# SystemStatusBoard.net
KiCad netlist of a schematic drawn in Altium Designer
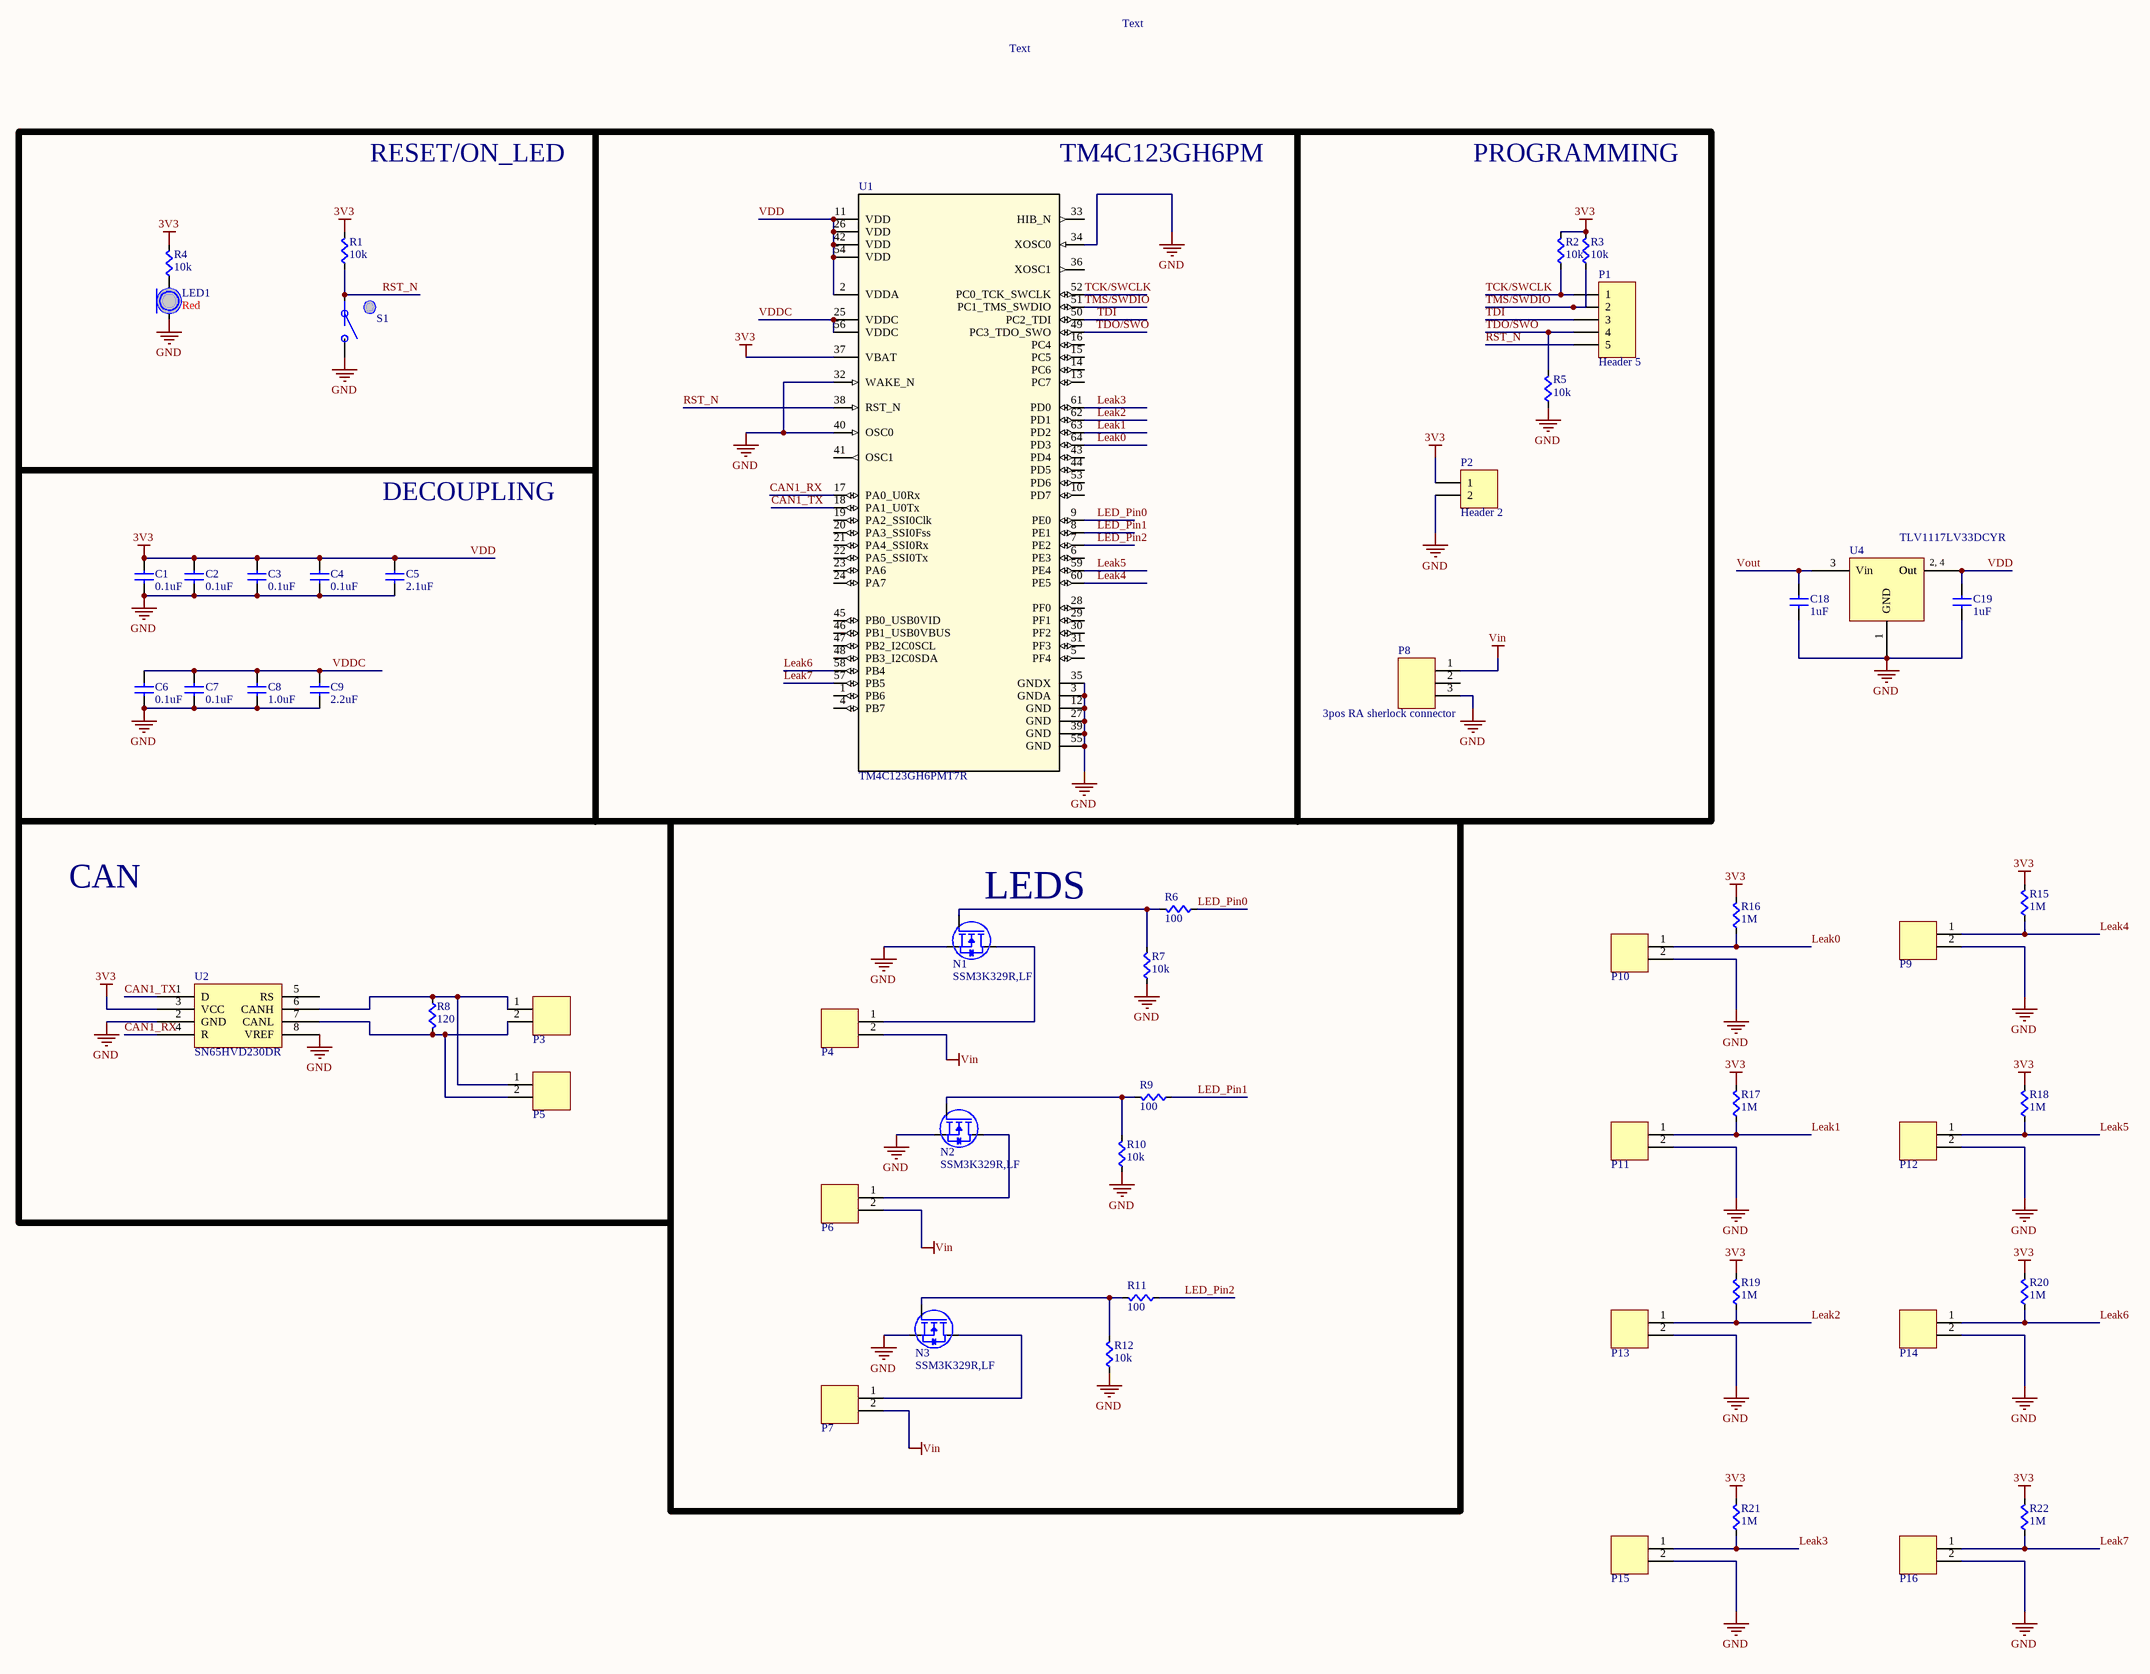
[diagram p0: SystemStatusBoard.SchDoc]

(export (version "E")
  (design (tool "Eeschema 10.0.6"))
  (components
    (comp (ref "C1")
      (value "0.1uF")
      (footprint "CAPC0603")
      (fields (field (name "Comment") "Cap"))
      (libsource (lib "SubjuGator8") (part "Cap"))
    )
    (comp (ref "C2")
      (value "0.1uF")
      (footprint "CAPC0603")
      (fields (field (name "Comment") "Cap"))
      (libsource (lib "SubjuGator8") (part "Cap"))
    )
    (comp (ref "C3")
      (value "0.1uF")
      (footprint "CAPC0603")
      (fields (field (name "Comment") "Cap"))
      (libsource (lib "SubjuGator8") (part "Cap"))
    )
    (comp (ref "C4")
      (value "0.1uF")
      (footprint "CAPC0603")
      (fields (field (name "Comment") "Cap"))
      (libsource (lib "SubjuGator8") (part "Cap"))
    )
    (comp (ref "C5")
      (value "2.1uF")
      (footprint "CAPC0603")
      (fields (field (name "Comment") "Cap"))
      (libsource (lib "SubjuGator8") (part "Cap"))
    )
    (comp (ref "C6")
      (value "0.1uF")
      (footprint "CAPC0603")
      (fields (field (name "Comment") "Cap"))
      (libsource (lib "SubjuGator8") (part "Cap"))
    )
    (comp (ref "C7")
      (value "0.1uF")
      (footprint "CAPC0603")
      (fields (field (name "Comment") "Cap"))
      (libsource (lib "SubjuGator8") (part "Cap"))
    )
    (comp (ref "C8")
      (value "1.0uF")
      (footprint "CAPC0603")
      (fields (field (name "Comment") "Cap"))
      (libsource (lib "SubjuGator8") (part "Cap"))
    )
    (comp (ref "C9")
      (value "2.2uF")
      (footprint "CAPC0603")
      (fields (field (name "Comment") "Cap"))
      (libsource (lib "SubjuGator8") (part "Cap"))
    )
    (comp (ref "C18")
      (value "1uF")
      (footprint "CAPC0603")
      (fields (field (name "MANUFACTURER PART NUMBER") "C0603C105K8PACTU") (field (name "Comment") "Cap"))
      (libsource (lib "SubjuGator8") (part "Cap"))
    )
    (comp (ref "C19")
      (value "1uF")
      (footprint "CAPC0603")
      (fields (field (name "MANUFACTURER PART NUMBER") "C0603C105K8PACTU") (field (name "Comment") "Cap"))
      (libsource (lib "SubjuGator8") (part "Cap"))
    )
    (comp (ref "LED1")
      (value "LED")
      (footprint "LED0603")
      (fields (field (name "COLOR") "Red"))
      (libsource (lib "SubjuGator8") (part "LED"))
    )
    (comp (ref "N1")
      (value "SSM3K329R,LF")
      (footprint "SSM3K329R,LF")
      (description "MOSFET N CH 30V 3.5A 2-3Z1A")
      (libsource (lib "SubjuGator8") (part "SSM3K329R,LF"))
    )
    (comp (ref "N2")
      (value "SSM3K329R,LF")
      (footprint "SSM3K329R,LF")
      (description "MOSFET N CH 30V 3.5A 2-3Z1A")
      (libsource (lib "SubjuGator8") (part "SSM3K329R,LF"))
    )
    (comp (ref "N3")
      (value "SSM3K329R,LF")
      (footprint "SSM3K329R,LF")
      (description "MOSFET N CH 30V 3.5A 2-3Z1A")
      (libsource (lib "SubjuGator8") (part "SSM3K329R,LF"))
    )
    (comp (ref "P1")
      (value "Header 5")
      (footprint "HDR1X5")
      (description "Header, 5-Pin")
      (fields (field (name "PUBLISHER") "Altium Limited"))
      (libsource (lib "Miscellaneous Connectors") (part "Header 5"))
    )
    (comp (ref "P2")
      (value "Header 2")
      (footprint "HDR1X2")
      (description "Header, 2-Pin")
      (fields (field (name "PUBLISHER") "Altium Limited"))
      (libsource (lib "Miscellaneous Connectors") (part "Header 2"))
    )
    (comp (ref "P3")
      (value "2-pin Horz Sherlock")
      (footprint "MOLEX-HDR-1X2-SHERLOCK-HORZ")
      (fields
        (field (name "MANUFACTURER PART NUMBER") "0353630260")
        (field (name "MANUFACTURER") "Molex Inc")
      )
      (libsource (lib "SubjuGator8") (part "MOLEX-HDR-1x2-SHERLOCK_RA"))
    )
    (comp (ref "P4")
      (value "2-pin Vert Sherlock")
      (footprint "MOLEX-HDR-1X2-SHERLOCK-VERT")
      (libsource (lib "SubjuGator8") (part "MOLEX-HDR-1x2-SHERLOCK_VERT"))
    )
    (comp (ref "P5")
      (value "2-pin Horz Sherlock")
      (footprint "MOLEX-HDR-1X2-SHERLOCK-HORZ")
      (fields
        (field (name "MANUFACTURER PART NUMBER") "0353630260")
        (field (name "MANUFACTURER") "Molex Inc")
      )
      (libsource (lib "SubjuGator8") (part "MOLEX-HDR-1x2-SHERLOCK_RA"))
    )
    (comp (ref "P6")
      (value "2-pin Vert Sherlock")
      (footprint "MOLEX-HDR-1X2-SHERLOCK-VERT")
      (libsource (lib "SubjuGator8") (part "MOLEX-HDR-1x2-SHERLOCK_VERT"))
    )
    (comp (ref "P7")
      (value "2-pin Vert Sherlock")
      (footprint "MOLEX-HDR-1X2-SHERLOCK-VERT")
      (libsource (lib "SubjuGator8") (part "MOLEX-HDR-1x2-SHERLOCK_VERT"))
    )
    (comp (ref "P8")
      (value "3pos RA sherlock connector")
      (footprint "MOLEX-HDR-1X3-SHERLOCK-RA")
      (description "Header, Molex, 2mm Pitch Sherlock Header, Single Row, Right Angle 3 Circuits, Length 3.3mm")
      (fields
        (field (name "MANUFACTURER PART NUMBER") "35363-0360")
        (field (name "MANUFACTURER") "Molex Connector Corporation")
      )
      (libsource (lib "SubjuGator8") (part "MOLEX-HDR-1x3-SHERLOCK_RA"))
    )
    (comp (ref "P9")
      (value "2-pin Vert Sherlock")
      (footprint "MOLEX-HDR-1X2-SHERLOCK-VERT")
      (libsource (lib "SubjuGator8") (part "MOLEX-HDR-1x2-SHERLOCK_VERT"))
    )
    (comp (ref "P10")
      (value "2-pin Vert Sherlock")
      (footprint "MOLEX-HDR-1X2-SHERLOCK-VERT")
      (libsource (lib "SubjuGator8") (part "MOLEX-HDR-1x2-SHERLOCK_VERT"))
    )
    (comp (ref "P11")
      (value "2-pin Vert Sherlock")
      (footprint "MOLEX-HDR-1X2-SHERLOCK-VERT")
      (libsource (lib "SubjuGator8") (part "MOLEX-HDR-1x2-SHERLOCK_VERT"))
    )
    (comp (ref "P12")
      (value "2-pin Vert Sherlock")
      (footprint "MOLEX-HDR-1X2-SHERLOCK-VERT")
      (libsource (lib "SubjuGator8") (part "MOLEX-HDR-1x2-SHERLOCK_VERT"))
    )
    (comp (ref "P13")
      (value "2-pin Vert Sherlock")
      (footprint "MOLEX-HDR-1X2-SHERLOCK-VERT")
      (libsource (lib "SubjuGator8") (part "MOLEX-HDR-1x2-SHERLOCK_VERT"))
    )
    (comp (ref "P14")
      (value "2-pin Vert Sherlock")
      (footprint "MOLEX-HDR-1X2-SHERLOCK-VERT")
      (libsource (lib "SubjuGator8") (part "MOLEX-HDR-1x2-SHERLOCK_VERT"))
    )
    (comp (ref "P15")
      (value "2-pin Vert Sherlock")
      (footprint "MOLEX-HDR-1X2-SHERLOCK-VERT")
      (libsource (lib "SubjuGator8") (part "MOLEX-HDR-1x2-SHERLOCK_VERT"))
    )
    (comp (ref "P16")
      (value "2-pin Vert Sherlock")
      (footprint "MOLEX-HDR-1X2-SHERLOCK-VERT")
      (libsource (lib "SubjuGator8") (part "MOLEX-HDR-1x2-SHERLOCK_VERT"))
    )
    (comp (ref "R1")
      (value "10k")
      (footprint "RES0603")
      (fields (field (name "Comment") "Res"))
      (libsource (lib "SubjuGator8") (part "Res"))
    )
    (comp (ref "R2")
      (value "10k")
      (footprint "RES0603")
      (fields (field (name "Comment") "Res"))
      (libsource (lib "SubjuGator8") (part "Res"))
    )
    (comp (ref "R3")
      (value "10k")
      (footprint "RES0603")
      (fields (field (name "Comment") "Res"))
      (libsource (lib "SubjuGator8") (part "Res"))
    )
    (comp (ref "R4")
      (value "10k")
      (footprint "RES0603")
      (fields (field (name "Comment") "Res"))
      (libsource (lib "SubjuGator8") (part "Res"))
    )
    (comp (ref "R5")
      (value "10k")
      (footprint "RES0603")
      (fields (field (name "Comment") "Res"))
      (libsource (lib "SubjuGator8") (part "Res"))
    )
    (comp (ref "R6")
      (value "100")
      (footprint "RES0603")
      (fields (field (name "Comment") "Res"))
      (libsource (lib "SubjuGator8") (part "Res"))
    )
    (comp (ref "R7")
      (value "10k")
      (footprint "RES0603")
      (fields (field (name "Comment") "Res"))
      (libsource (lib "SubjuGator8") (part "Res"))
    )
    (comp (ref "R8")
      (value "120")
      (footprint "RES0603")
      (fields (field (name "Comment") "Res"))
      (libsource (lib "SubjuGator8") (part "Res"))
    )
    (comp (ref "R9")
      (value "100")
      (footprint "RES0603")
      (fields (field (name "Comment") "Res"))
      (libsource (lib "SubjuGator8") (part "Res"))
    )
    (comp (ref "R10")
      (value "10k")
      (footprint "RES0603")
      (fields (field (name "Comment") "Res"))
      (libsource (lib "SubjuGator8") (part "Res"))
    )
    (comp (ref "R11")
      (value "100")
      (footprint "RES0603")
      (fields (field (name "Comment") "Res"))
      (libsource (lib "SubjuGator8") (part "Res"))
    )
    (comp (ref "R12")
      (value "10k")
      (footprint "RES0603")
      (fields (field (name "Comment") "Res"))
      (libsource (lib "SubjuGator8") (part "Res"))
    )
    (comp (ref "R15")
      (value "1M")
      (footprint "RES0603")
      (fields (field (name "Comment") "Res"))
      (libsource (lib "SubjuGator8") (part "Res"))
    )
    (comp (ref "R16")
      (value "1M")
      (footprint "RES0603")
      (fields (field (name "Comment") "Res"))
      (libsource (lib "SubjuGator8") (part "Res"))
    )
    (comp (ref "R17")
      (value "1M")
      (footprint "RES0603")
      (fields (field (name "Comment") "Res"))
      (libsource (lib "SubjuGator8") (part "Res"))
    )
    (comp (ref "R18")
      (value "1M")
      (footprint "RES0603")
      (fields (field (name "Comment") "Res"))
      (libsource (lib "SubjuGator8") (part "Res"))
    )
    (comp (ref "R19")
      (value "1M")
      (footprint "RES0603")
      (fields (field (name "Comment") "Res"))
      (libsource (lib "SubjuGator8") (part "Res"))
    )
    (comp (ref "R20")
      (value "1M")
      (footprint "RES0603")
      (fields (field (name "Comment") "Res"))
      (libsource (lib "SubjuGator8") (part "Res"))
    )
    (comp (ref "R21")
      (value "1M")
      (footprint "RES0603")
      (fields (field (name "Comment") "Res"))
      (libsource (lib "SubjuGator8") (part "Res"))
    )
    (comp (ref "R22")
      (value "1M")
      (footprint "RES0603")
      (fields (field (name "Comment") "Res"))
      (libsource (lib "SubjuGator8") (part "Res"))
    )
    (comp (ref "S1")
      (value "Button")
      (footprint "PTS645xxxxSMTR92")
      (description "SPST Button")
      (libsource (lib "SubjuGator8") (part "Button"))
    )
    (comp (ref "U1")
      (value "TM4C123GH6PMT7R")
      (footprint "PM0064A_N")
      (description "Imported")
      (fields
        (field (name "PARTNUMBER") "TM4C123GH6PMTR")
        (field (name "ALTERNATE_PARTNUMBER") "TM4C123GH6PMT")
      )
      (libsource (lib "TivaC") (part "TM4C123GH6PMT7R"))
    )
    (comp (ref "U2")
      (value "SN65HVD230DR")
      (footprint "SOIC-8pin")
      (description "IC TXRX CAN 1MBPS 3.3V 8SOIC")
      (libsource (lib "SubjuGator8") (part "SN65HVD230DR"))
    )
    (comp (ref "U4")
      (value "TLV1117LV33DCYR")
      (footprint "SOT23-4N")
      (description "IC REG LINEAR 3.3V 1A SOT223-4")
      (fields (field (name "DIGI-KEY PART NUMBER") "296-28778-1-ND"))
      (libsource (lib "ICs") (part "TLV1117LV33DCYR"))
    )
  )
  (nets
    (net (code "1") (name "/CAN1_RX") (class "Default")
      (node (ref "U1") (pin "17") (pinfunction "PA0_U0Rx_17") (pintype "bidirectional"))
      (node (ref "U2") (pin "4") (pinfunction "R_4") (pintype "passive"))
    )
    (net (code "2") (name "/CAN1_TX") (class "Default")
      (node (ref "U1") (pin "18") (pinfunction "PA1_U0Tx_18") (pintype "bidirectional"))
      (node (ref "U2") (pin "1") (pinfunction "D_1") (pintype "passive"))
    )
    (net (code "3") (name "/LED_Pin0") (class "Default")
      (node (ref "R6") (pin "2") (pinfunction "B_2") (pintype "passive"))
      (node (ref "U1") (pin "9") (pinfunction "PE0_9") (pintype "bidirectional"))
    )
    (net (code "4") (name "/LED_Pin1") (class "Default")
      (node (ref "R9") (pin "2") (pinfunction "B_2") (pintype "passive"))
      (node (ref "U1") (pin "8") (pinfunction "PE1_8") (pintype "bidirectional"))
    )
    (net (code "5") (name "/LED_Pin2") (class "Default")
      (node (ref "R11") (pin "2") (pinfunction "B_2") (pintype "passive"))
      (node (ref "U1") (pin "7") (pinfunction "PE2_7") (pintype "bidirectional"))
    )
    (net (code "6") (name "/Leak0") (class "Default")
      (node (ref "P10") (pin "1") (pinfunction "1_1") (pintype "passive"))
      (node (ref "R16") (pin "2") (pinfunction "B_2") (pintype "passive"))
      (node (ref "U1") (pin "64") (pinfunction "PD3_64") (pintype "bidirectional"))
    )
    (net (code "7") (name "/Leak1") (class "Default")
      (node (ref "P11") (pin "1") (pinfunction "1_1") (pintype "passive"))
      (node (ref "R17") (pin "2") (pinfunction "B_2") (pintype "passive"))
      (node (ref "U1") (pin "63") (pinfunction "PD2_63") (pintype "bidirectional"))
    )
    (net (code "8") (name "/Leak2") (class "Default")
      (node (ref "P13") (pin "1") (pinfunction "1_1") (pintype "passive"))
      (node (ref "R19") (pin "2") (pinfunction "B_2") (pintype "passive"))
      (node (ref "U1") (pin "62") (pinfunction "PD1_62") (pintype "bidirectional"))
    )
    (net (code "9") (name "/Leak3") (class "Default")
      (node (ref "P15") (pin "1") (pinfunction "1_1") (pintype "passive"))
      (node (ref "R21") (pin "2") (pinfunction "B_2") (pintype "passive"))
      (node (ref "U1") (pin "61") (pinfunction "PD0_61") (pintype "bidirectional"))
    )
    (net (code "10") (name "/Leak4") (class "Default")
      (node (ref "P9") (pin "1") (pinfunction "1_1") (pintype "passive"))
      (node (ref "R15") (pin "2") (pinfunction "B_2") (pintype "passive"))
      (node (ref "U1") (pin "60") (pinfunction "PE5_60") (pintype "bidirectional"))
    )
    (net (code "11") (name "/Leak5") (class "Default")
      (node (ref "P12") (pin "1") (pinfunction "1_1") (pintype "passive"))
      (node (ref "R18") (pin "2") (pinfunction "B_2") (pintype "passive"))
      (node (ref "U1") (pin "59") (pinfunction "PE4_59") (pintype "bidirectional"))
    )
    (net (code "12") (name "/Leak6") (class "Default")
      (node (ref "P14") (pin "1") (pinfunction "1_1") (pintype "passive"))
      (node (ref "R20") (pin "2") (pinfunction "B_2") (pintype "passive"))
      (node (ref "U1") (pin "58") (pinfunction "PB4_58") (pintype "bidirectional"))
    )
    (net (code "13") (name "/Leak7") (class "Default")
      (node (ref "P16") (pin "1") (pinfunction "1_1") (pintype "passive"))
      (node (ref "R22") (pin "2") (pinfunction "B_2") (pintype "passive"))
      (node (ref "U1") (pin "57") (pinfunction "PB5_57") (pintype "bidirectional"))
    )
    (net (code "14") (name "/RST_N") (class "Default")
      (node (ref "P1") (pin "5") (pinfunction "5_5") (pintype "passive"))
      (node (ref "R1") (pin "2") (pinfunction "B_2") (pintype "passive"))
      (node (ref "S1") (pin "A") (pinfunction "A_A") (pintype "passive"))
      (node (ref "U1") (pin "38") (pinfunction "RST_N_38") (pintype "input"))
    )
    (net (code "15") (name "/TCK{slash}SWCLK") (class "Default")
      (node (ref "P1") (pin "1") (pinfunction "1_1") (pintype "passive"))
      (node (ref "R2") (pin "2") (pinfunction "B_2") (pintype "passive"))
      (node (ref "U1") (pin "52") (pinfunction "PC0_TCK_SWCLK_52") (pintype "bidirectional"))
    )
    (net (code "16") (name "/TDI") (class "Default")
      (node (ref "P1") (pin "3") (pinfunction "3_3") (pintype "passive"))
      (node (ref "U1") (pin "50") (pinfunction "PC2_TDI_50") (pintype "bidirectional"))
    )
    (net (code "17") (name "/TDO{slash}SWO") (class "Default")
      (node (ref "P1") (pin "4") (pinfunction "4_4") (pintype "passive"))
      (node (ref "R5") (pin "1") (pinfunction "A_1") (pintype "passive"))
      (node (ref "U1") (pin "49") (pinfunction "PC3_TDO_SWO_49") (pintype "bidirectional"))
    )
    (net (code "18") (name "/TMS{slash}SWDIO") (class "Default")
      (node (ref "P1") (pin "2") (pinfunction "2_2") (pintype "passive"))
      (node (ref "R3") (pin "2") (pinfunction "B_2") (pintype "passive"))
      (node (ref "U1") (pin "51") (pinfunction "PC1_TMS_SWDIO_51") (pintype "bidirectional"))
    )
    (net (code "19") (name "/VDDC") (class "Default")
      (node (ref "C6") (pin "1") (pinfunction "A_1") (pintype "passive"))
      (node (ref "C7") (pin "1") (pinfunction "A_1") (pintype "passive"))
      (node (ref "C8") (pin "1") (pinfunction "A_1") (pintype "passive"))
      (node (ref "C9") (pin "1") (pinfunction "A_1") (pintype "passive"))
      (node (ref "U1") (pin "25") (pinfunction "VDDC_25") (pintype "power_in"))
      (node (ref "U1") (pin "56") (pinfunction "VDDC_56") (pintype "power_in"))
    )
    (net (code "20") (name "/Vout") (class "Default")
      (node (ref "C18") (pin "1") (pinfunction "A_1") (pintype "passive"))
      (node (ref "U4") (pin "3") (pinfunction "Vin_3") (pintype "passive"))
    )
    (net (code "21") (name "3V3") (class "Default")
      (node (ref "C1") (pin "1") (pinfunction "A_1") (pintype "passive"))
      (node (ref "C19") (pin "1") (pinfunction "A_1") (pintype "passive"))
      (node (ref "C2") (pin "1") (pinfunction "A_1") (pintype "passive"))
      (node (ref "C3") (pin "1") (pinfunction "A_1") (pintype "passive"))
      (node (ref "C4") (pin "1") (pinfunction "A_1") (pintype "passive"))
      (node (ref "C5") (pin "1") (pinfunction "A_1") (pintype "passive"))
      (node (ref "P2") (pin "1") (pinfunction "1_1") (pintype "passive"))
      (node (ref "R1") (pin "1") (pinfunction "A_1") (pintype "passive"))
      (node (ref "R15") (pin "1") (pinfunction "A_1") (pintype "passive"))
      (node (ref "R16") (pin "1") (pinfunction "A_1") (pintype "passive"))
      (node (ref "R17") (pin "1") (pinfunction "A_1") (pintype "passive"))
      (node (ref "R18") (pin "1") (pinfunction "A_1") (pintype "passive"))
      (node (ref "R19") (pin "1") (pinfunction "A_1") (pintype "passive"))
      (node (ref "R2") (pin "1") (pinfunction "A_1") (pintype "passive"))
      (node (ref "R20") (pin "1") (pinfunction "A_1") (pintype "passive"))
      (node (ref "R21") (pin "1") (pinfunction "A_1") (pintype "passive"))
      (node (ref "R22") (pin "1") (pinfunction "A_1") (pintype "passive"))
      (node (ref "R3") (pin "1") (pinfunction "A_1") (pintype "passive"))
      (node (ref "R4") (pin "1") (pinfunction "A_1") (pintype "passive"))
      (node (ref "U1") (pin "11") (pinfunction "VDD_11") (pintype "power_in"))
      (node (ref "U1") (pin "2") (pinfunction "VDDA_2") (pintype "power_in"))
      (node (ref "U1") (pin "26") (pinfunction "VDD_26") (pintype "power_in"))
      (node (ref "U1") (pin "37") (pinfunction "VBAT_37") (pintype "power_in"))
      (node (ref "U1") (pin "42") (pinfunction "VDD_42") (pintype "power_in"))
      (node (ref "U1") (pin "54") (pinfunction "VDD_54") (pintype "power_in"))
      (node (ref "U2") (pin "3") (pinfunction "VCC_3") (pintype "passive"))
      (node (ref "U4") (pin "2") (pinfunction "Out_2") (pintype "passive"))
      (node (ref "U4") (pin "4") (pinfunction "Out_4") (pintype "passive"))
    )
    (net (code "22") (name "GND") (class "Default")
      (node (ref "C1") (pin "2") (pinfunction "B_2") (pintype "passive"))
      (node (ref "C18") (pin "2") (pinfunction "B_2") (pintype "passive"))
      (node (ref "C19") (pin "2") (pinfunction "B_2") (pintype "passive"))
      (node (ref "C2") (pin "2") (pinfunction "B_2") (pintype "passive"))
      (node (ref "C3") (pin "2") (pinfunction "B_2") (pintype "passive"))
      (node (ref "C4") (pin "2") (pinfunction "B_2") (pintype "passive"))
      (node (ref "C5") (pin "2") (pinfunction "B_2") (pintype "passive"))
      (node (ref "C6") (pin "2") (pinfunction "B_2") (pintype "passive"))
      (node (ref "C7") (pin "2") (pinfunction "B_2") (pintype "passive"))
      (node (ref "C8") (pin "2") (pinfunction "B_2") (pintype "passive"))
      (node (ref "C9") (pin "2") (pinfunction "B_2") (pintype "passive"))
      (node (ref "LED1") (pin "C") (pinfunction "C_C") (pintype "passive"))
      (node (ref "N1") (pin "2") (pinfunction "S_2") (pintype "passive"))
      (node (ref "N2") (pin "2") (pinfunction "S_2") (pintype "passive"))
      (node (ref "N3") (pin "2") (pinfunction "S_2") (pintype "passive"))
      (node (ref "P10") (pin "2") (pinfunction "2_2") (pintype "passive"))
      (node (ref "P11") (pin "2") (pinfunction "2_2") (pintype "passive"))
      (node (ref "P12") (pin "2") (pinfunction "2_2") (pintype "passive"))
      (node (ref "P13") (pin "2") (pinfunction "2_2") (pintype "passive"))
      (node (ref "P14") (pin "2") (pinfunction "2_2") (pintype "passive"))
      (node (ref "P15") (pin "2") (pinfunction "2_2") (pintype "passive"))
      (node (ref "P16") (pin "2") (pinfunction "2_2") (pintype "passive"))
      (node (ref "P2") (pin "2") (pinfunction "2_2") (pintype "passive"))
      (node (ref "P8") (pin "3") (pinfunction "3_3") (pintype "passive"))
      (node (ref "P9") (pin "2") (pinfunction "2_2") (pintype "passive"))
      (node (ref "R10") (pin "2") (pinfunction "B_2") (pintype "passive"))
      (node (ref "R12") (pin "2") (pinfunction "B_2") (pintype "passive"))
      (node (ref "R5") (pin "2") (pinfunction "B_2") (pintype "passive"))
      (node (ref "R7") (pin "2") (pinfunction "B_2") (pintype "passive"))
      (node (ref "S1") (pin "B") (pinfunction "B_B") (pintype "passive"))
      (node (ref "U1") (pin "12") (pinfunction "GND_12") (pintype "power_in"))
      (node (ref "U1") (pin "27") (pinfunction "GND_27") (pintype "power_in"))
      (node (ref "U1") (pin "3") (pinfunction "GNDA_3") (pintype "power_in"))
      (node (ref "U1") (pin "32") (pinfunction "WAKE_N_32") (pintype "input"))
      (node (ref "U1") (pin "34") (pinfunction "XOSC0_34") (pintype "input"))
      (node (ref "U1") (pin "35") (pinfunction "GNDX_35") (pintype "power_in"))
      (node (ref "U1") (pin "39") (pinfunction "GND_39") (pintype "power_in"))
      (node (ref "U1") (pin "40") (pinfunction "OSC0_40") (pintype "input"))
      (node (ref "U1") (pin "55") (pinfunction "GND_55") (pintype "power_in"))
      (node (ref "U2") (pin "2") (pinfunction "GND_2") (pintype "passive"))
      (node (ref "U2") (pin "8") (pinfunction "VREF_8") (pintype "passive"))
      (node (ref "U4") (pin "1") (pinfunction "GND_1") (pintype "passive"))
    )
    (net (code "23") (name "Net-(N1-D)") (class "Default")
      (node (ref "N1") (pin "3") (pinfunction "D_3") (pintype "passive"))
      (node (ref "P4") (pin "1") (pinfunction "1_1") (pintype "passive"))
    )
    (net (code "24") (name "Net-(N1-G)") (class "Default")
      (node (ref "N1") (pin "1") (pinfunction "G_1") (pintype "passive"))
      (node (ref "R6") (pin "1") (pinfunction "A_1") (pintype "passive"))
      (node (ref "R7") (pin "1") (pinfunction "A_1") (pintype "passive"))
    )
    (net (code "25") (name "Net-(N2-D)") (class "Default")
      (node (ref "N2") (pin "3") (pinfunction "D_3") (pintype "passive"))
      (node (ref "P6") (pin "1") (pinfunction "1_1") (pintype "passive"))
    )
    (net (code "26") (name "Net-(N2-G)") (class "Default")
      (node (ref "N2") (pin "1") (pinfunction "G_1") (pintype "passive"))
      (node (ref "R10") (pin "1") (pinfunction "A_1") (pintype "passive"))
      (node (ref "R9") (pin "1") (pinfunction "A_1") (pintype "passive"))
    )
    (net (code "27") (name "Net-(N3-D)") (class "Default")
      (node (ref "N3") (pin "3") (pinfunction "D_3") (pintype "passive"))
      (node (ref "P7") (pin "1") (pinfunction "1_1") (pintype "passive"))
    )
    (net (code "28") (name "Net-(N3-G)") (class "Default")
      (node (ref "N3") (pin "1") (pinfunction "G_1") (pintype "passive"))
      (node (ref "R11") (pin "1") (pinfunction "A_1") (pintype "passive"))
      (node (ref "R12") (pin "1") (pinfunction "A_1") (pintype "passive"))
    )
    (net (code "29") (name "Net-(R4-B)") (class "Default")
      (node (ref "LED1") (pin "A") (pinfunction "A_A") (pintype "passive"))
      (node (ref "R4") (pin "2") (pinfunction "B_2") (pintype "passive"))
    )
    (net (code "30") (name "Net-(R8-A)") (class "Default")
      (node (ref "P3") (pin "2") (pinfunction "2_2") (pintype "passive"))
      (node (ref "P5") (pin "2") (pinfunction "2_2") (pintype "passive"))
      (node (ref "R8") (pin "1") (pinfunction "A_1") (pintype "passive"))
      (node (ref "U2") (pin "7") (pinfunction "CANL_7") (pintype "passive"))
    )
    (net (code "31") (name "Net-(R8-B)") (class "Default")
      (node (ref "P3") (pin "1") (pinfunction "1_1") (pintype "passive"))
      (node (ref "P5") (pin "1") (pinfunction "1_1") (pintype "passive"))
      (node (ref "R8") (pin "2") (pinfunction "B_2") (pintype "passive"))
      (node (ref "U2") (pin "6") (pinfunction "CANH_6") (pintype "passive"))
    )
    (net (code "32") (name "Vin") (class "Default")
      (node (ref "P4") (pin "2") (pinfunction "2_2") (pintype "passive"))
      (node (ref "P6") (pin "2") (pinfunction "2_2") (pintype "passive"))
      (node (ref "P7") (pin "2") (pinfunction "2_2") (pintype "passive"))
      (node (ref "P8") (pin "1") (pinfunction "1_1") (pintype "passive"))
    )
    (net (code "33") (name "unconnected-(P8-Pad2)") (class "Default")
      (node (ref "P8") (pin "2") (pinfunction "2_2") (pintype "passive"))
    )
    (net (code "34") (name "unconnected-(U1-HIB_N-Pad33)") (class "Default")
      (node (ref "U1") (pin "33") (pinfunction "HIB_N_33") (pintype "output"))
    )
    (net (code "35") (name "unconnected-(U1-OSC1-Pad41)") (class "Default")
      (node (ref "U1") (pin "41") (pinfunction "OSC1_41") (pintype "output"))
    )
    (net (code "36") (name "unconnected-(U1-PA2_SSI0Clk-Pad19)") (class "Default")
      (node (ref "U1") (pin "19") (pinfunction "PA2_SSI0Clk_19") (pintype "bidirectional"))
    )
    (net (code "37") (name "unconnected-(U1-PA3_SSI0Fss-Pad20)") (class "Default")
      (node (ref "U1") (pin "20") (pinfunction "PA3_SSI0Fss_20") (pintype "bidirectional"))
    )
    (net (code "38") (name "unconnected-(U1-PA4_SSI0Rx-Pad21)") (class "Default")
      (node (ref "U1") (pin "21") (pinfunction "PA4_SSI0Rx_21") (pintype "bidirectional"))
    )
    (net (code "39") (name "unconnected-(U1-PA5_SSI0Tx-Pad22)") (class "Default")
      (node (ref "U1") (pin "22") (pinfunction "PA5_SSI0Tx_22") (pintype "bidirectional"))
    )
    (net (code "40") (name "unconnected-(U1-PA6-Pad23)") (class "Default")
      (node (ref "U1") (pin "23") (pinfunction "PA6_23") (pintype "bidirectional"))
    )
    (net (code "41") (name "unconnected-(U1-PA7-Pad24)") (class "Default")
      (node (ref "U1") (pin "24") (pinfunction "PA7_24") (pintype "bidirectional"))
    )
    (net (code "42") (name "unconnected-(U1-PB0_USB0VID-Pad45)") (class "Default")
      (node (ref "U1") (pin "45") (pinfunction "PB0_USB0VID_45") (pintype "bidirectional"))
    )
    (net (code "43") (name "unconnected-(U1-PB1_USB0VBUS-Pad46)") (class "Default")
      (node (ref "U1") (pin "46") (pinfunction "PB1_USB0VBUS_46") (pintype "bidirectional"))
    )
    (net (code "44") (name "unconnected-(U1-PB2_I2C0SCL-Pad47)") (class "Default")
      (node (ref "U1") (pin "47") (pinfunction "PB2_I2C0SCL_47") (pintype "bidirectional"))
    )
    (net (code "45") (name "unconnected-(U1-PB3_I2C0SDA-Pad48)") (class "Default")
      (node (ref "U1") (pin "48") (pinfunction "PB3_I2C0SDA_48") (pintype "bidirectional"))
    )
    (net (code "46") (name "unconnected-(U1-PB6-Pad1)") (class "Default")
      (node (ref "U1") (pin "1") (pinfunction "PB6_1") (pintype "bidirectional"))
    )
    (net (code "47") (name "unconnected-(U1-PB7-Pad4)") (class "Default")
      (node (ref "U1") (pin "4") (pinfunction "PB7_4") (pintype "bidirectional"))
    )
    (net (code "48") (name "unconnected-(U1-PC4-Pad16)") (class "Default")
      (node (ref "U1") (pin "16") (pinfunction "PC4_16") (pintype "bidirectional"))
    )
    (net (code "49") (name "unconnected-(U1-PC5-Pad15)") (class "Default")
      (node (ref "U1") (pin "15") (pinfunction "PC5_15") (pintype "bidirectional"))
    )
    (net (code "50") (name "unconnected-(U1-PC6-Pad14)") (class "Default")
      (node (ref "U1") (pin "14") (pinfunction "PC6_14") (pintype "bidirectional"))
    )
    (net (code "51") (name "unconnected-(U1-PC7-Pad13)") (class "Default")
      (node (ref "U1") (pin "13") (pinfunction "PC7_13") (pintype "bidirectional"))
    )
    (net (code "52") (name "unconnected-(U1-PD4-Pad43)") (class "Default")
      (node (ref "U1") (pin "43") (pinfunction "PD4_43") (pintype "bidirectional"))
    )
    (net (code "53") (name "unconnected-(U1-PD5-Pad44)") (class "Default")
      (node (ref "U1") (pin "44") (pinfunction "PD5_44") (pintype "bidirectional"))
    )
    (net (code "54") (name "unconnected-(U1-PD6-Pad53)") (class "Default")
      (node (ref "U1") (pin "53") (pinfunction "PD6_53") (pintype "bidirectional"))
    )
    (net (code "55") (name "unconnected-(U1-PD7-Pad10)") (class "Default")
      (node (ref "U1") (pin "10") (pinfunction "PD7_10") (pintype "bidirectional"))
    )
    (net (code "56") (name "unconnected-(U1-PE3-Pad6)") (class "Default")
      (node (ref "U1") (pin "6") (pinfunction "PE3_6") (pintype "bidirectional"))
    )
    (net (code "57") (name "unconnected-(U1-PF0-Pad28)") (class "Default")
      (node (ref "U1") (pin "28") (pinfunction "PF0_28") (pintype "bidirectional"))
    )
    (net (code "58") (name "unconnected-(U1-PF1-Pad29)") (class "Default")
      (node (ref "U1") (pin "29") (pinfunction "PF1_29") (pintype "bidirectional"))
    )
    (net (code "59") (name "unconnected-(U1-PF2-Pad30)") (class "Default")
      (node (ref "U1") (pin "30") (pinfunction "PF2_30") (pintype "bidirectional"))
    )
    (net (code "60") (name "unconnected-(U1-PF3-Pad31)") (class "Default")
      (node (ref "U1") (pin "31") (pinfunction "PF3_31") (pintype "bidirectional"))
    )
    (net (code "61") (name "unconnected-(U1-PF4-Pad5)") (class "Default")
      (node (ref "U1") (pin "5") (pinfunction "PF4_5") (pintype "bidirectional"))
    )
    (net (code "62") (name "unconnected-(U1-XOSC1-Pad36)") (class "Default")
      (node (ref "U1") (pin "36") (pinfunction "XOSC1_36") (pintype "output"))
    )
    (net (code "63") (name "unconnected-(U2-RS-Pad5)") (class "Default")
      (node (ref "U2") (pin "5") (pinfunction "RS_5") (pintype "passive"))
    )
  )
)
